# Sheet1.net
KiCad netlist of a schematic drawn in Altium Designer
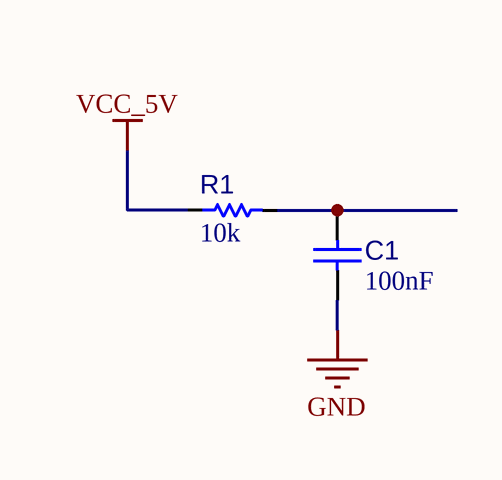
[diagram p0: Sheet1.SchDoc]

(export (version "E")
  (design (tool "Eeschema 10.0.6"))
  (components
    (comp (ref "C1")
      (value "100nF")
      (footprint "C_1608[0603]")
      (description "Capacitor type 1")
      (fields (field (name "TOLERANCE") "10%") (field (name "Comment") "Cap 100nF 0603"))
      (libsource (lib "TEP_243-Altium_DBLib") (part "capacitor"))
    )
    (comp (ref "R1")
      (value "10k")
      (footprint "R_1608[0603]")
      (description "Resistor type 1")
      (fields (field (name "TOLERANCE") "1%") (field (name "Comment") "Res 10k 1% 0603"))
      (libsource (lib "TEP_243-Altium_DBLib") (part "resistor"))
    )
  )
  (nets
    (net (code "1") (name "GND") (class "Default")
      (node (ref "C1") (pin "1") (pinfunction "1_1") (pintype "passive"))
    )
    (net (code "2") (name "Net-(C1-Pad2)") (class "Default")
      (node (ref "C1") (pin "2") (pinfunction "2_2") (pintype "passive"))
      (node (ref "R1") (pin "2") (pinfunction "2_2") (pintype "passive"))
    )
    (net (code "3") (name "VCC_5V") (class "Default")
      (node (ref "R1") (pin "1") (pinfunction "1_1") (pintype "passive"))
    )
  )
)
